# Servo_decoup.net
KiCad netlist of a schematic drawn in EAGLE
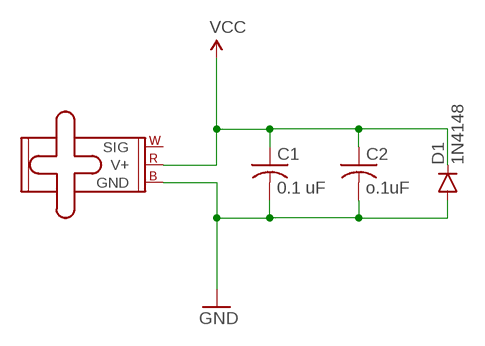
[diagram p0: schematic, sheet 1]

(export (version "E")
  (design (tool "Eeschema 10.0.6"))
  (components
    (comp (ref "C1")
      (value "0.1 uF")
      (footprint "eagle-import:C025-025X050")
      (libsource (lib "eagle-import") (part "C-US025-025X050"))
    )
    (comp (ref "C2")
      (value "o.1uF")
      (footprint "eagle-import:C025-025X050")
      (libsource (lib "eagle-import") (part "C-US025-025X050"))
    )
    (comp (ref "D1")
      (value "1N4148")
      (footprint "eagle-import:DIODE-1N4148")
      (libsource (lib "eagle-import") (part "DIODE1N4148"))
    )
    (comp (ref "M1")
      (value "SMALL_SERVO")
      (footprint "eagle-import:1X03")
      (libsource (lib "eagle-import") (part "SMALL_SERVO"))
    )
  )
  (nets
    (net (code "1") (name "GND") (class "Default")
      (node (ref "C1") (pin "2") (pinfunction "2_2") (pintype "passive"))
      (node (ref "C2") (pin "2") (pinfunction "2_2") (pintype "passive"))
      (node (ref "D1") (pin "A") (pinfunction "A_A") (pintype "passive"))
      (node (ref "M1") (pin "3") (pinfunction "GND_3") (pintype "bidirectional"))
    )
    (net (code "2") (name "VCC") (class "Default")
      (node (ref "C1") (pin "1") (pinfunction "1_1") (pintype "passive"))
      (node (ref "C2") (pin "1") (pinfunction "1_1") (pintype "passive"))
      (node (ref "D1") (pin "C") (pinfunction "C_C") (pintype "passive"))
      (node (ref "M1") (pin "2") (pinfunction "V+_2") (pintype "bidirectional"))
    )
    (net (code "3") (name "unconnected-(M1-SIG-Pad1)") (class "Default")
      (node (ref "M1") (pin "1") (pinfunction "SIG_1") (pintype "bidirectional"))
    )
  )
)
